# LPC1768.net
KiCad netlist of a schematic drawn in Altium Designer
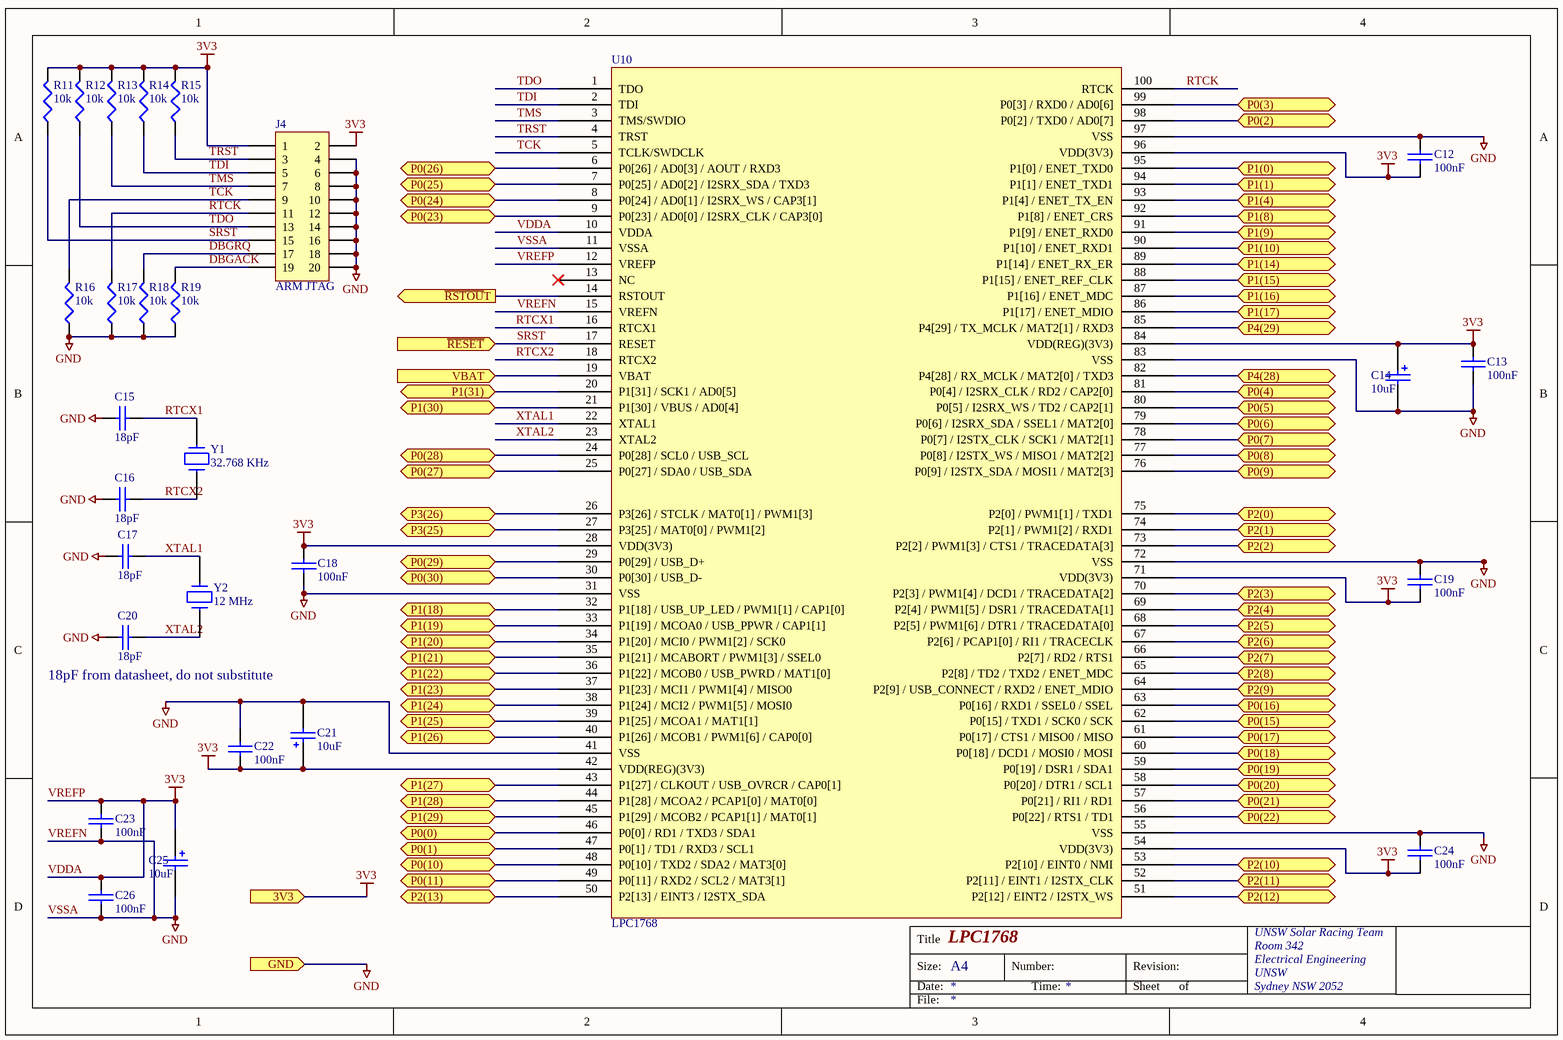
[diagram p0: LPC1768.SchDoc]

(export (version "E")
  (design (tool "Eeschema 10.0.6"))
  (components
    (comp (ref "C12")
      (value "100nF")
      (footprint "0603")
      (description "Capacitor")
      (libsource (lib "RCLDQ") (part "CAP"))
    )
    (comp (ref "C13")
      (value "100nF")
      (footprint "0603")
      (description "Capacitor")
      (libsource (lib "RCLDQ") (part "CAP"))
    )
    (comp (ref "C14")
      (value "10uF")
      (footprint "MCCT-CASEA")
      (description "Polarized Capacitor (Surface Mount)")
      (libsource (lib "RCLDQ") (part "CAP POL3"))
    )
    (comp (ref "C15")
      (value "18pF")
      (footprint "0603")
      (description "Capacitor")
      (libsource (lib "*") (part "CAP"))
    )
    (comp (ref "C16")
      (value "18pF")
      (footprint "0603")
      (description "Capacitor")
      (libsource (lib "*") (part "CAP"))
    )
    (comp (ref "C17")
      (value "18pF")
      (footprint "0603")
      (description "Capacitor")
      (libsource (lib "*") (part "CAP"))
    )
    (comp (ref "C18")
      (value "100nF")
      (footprint "0603")
      (description "Capacitor")
      (libsource (lib "RCLDQ") (part "CAP"))
    )
    (comp (ref "C19")
      (value "100nF")
      (footprint "0603")
      (description "Capacitor")
      (libsource (lib "RCLDQ") (part "CAP"))
    )
    (comp (ref "C20")
      (value "18pF")
      (footprint "0603")
      (description "Capacitor")
      (libsource (lib "*") (part "CAP"))
    )
    (comp (ref "C21")
      (value "10uF")
      (footprint "MCCT-CASEA")
      (description "Polarized Capacitor (Surface Mount)")
      (libsource (lib "RCLDQ") (part "CAP POL3"))
    )
    (comp (ref "C22")
      (value "100nF")
      (footprint "0603")
      (description "Capacitor")
      (libsource (lib "RCLDQ") (part "CAP"))
    )
    (comp (ref "C23")
      (value "100nF")
      (footprint "0603")
      (description "Capacitor")
      (libsource (lib "RCLDQ") (part "CAP"))
    )
    (comp (ref "C24")
      (value "100nF")
      (footprint "0603")
      (description "Capacitor")
      (libsource (lib "RCLDQ") (part "CAP"))
    )
    (comp (ref "C25")
      (value "10uF")
      (footprint "MCCT-CASEA")
      (description "Polarized Capacitor (Surface Mount)")
      (libsource (lib "RCLDQ") (part "CAP POL3"))
    )
    (comp (ref "C26")
      (value "100nF")
      (footprint "0603")
      (description "Capacitor")
      (libsource (lib "RCLDQ") (part "CAP"))
    )
    (comp (ref "J4")
      (value "ARM JTAG")
      (footprint "HDR2X10")
      (description "Header, 10-Pin, Dual row")
      (libsource (lib "Miscellaneous Connectors") (part "Header 10X2"))
    )
    (comp (ref "R11")
      (value "10k")
      (footprint "0603")
      (description "Resistor")
      (libsource (lib "RCLDQ") (part "RES1"))
    )
    (comp (ref "R12")
      (value "10k")
      (footprint "0603")
      (description "Resistor")
      (libsource (lib "RCLDQ") (part "RES1"))
    )
    (comp (ref "R13")
      (value "10k")
      (footprint "0603")
      (description "Resistor")
      (libsource (lib "RCLDQ") (part "RES1"))
    )
    (comp (ref "R14")
      (value "10k")
      (footprint "0603")
      (description "Resistor")
      (libsource (lib "RCLDQ") (part "RES1"))
    )
    (comp (ref "R15")
      (value "10k")
      (footprint "0603")
      (description "Resistor")
      (libsource (lib "RCLDQ") (part "RES1"))
    )
    (comp (ref "R16")
      (value "10k")
      (footprint "0603")
      (description "Resistor")
      (libsource (lib "RCLDQ") (part "RES1"))
    )
    (comp (ref "R17")
      (value "10k")
      (footprint "0603")
      (description "Resistor")
      (libsource (lib "RCLDQ") (part "RES1"))
    )
    (comp (ref "R18")
      (value "10k")
      (footprint "0603")
      (description "Resistor")
      (libsource (lib "RCLDQ") (part "RES1"))
    )
    (comp (ref "R19")
      (value "10k")
      (footprint "0603")
      (description "Resistor")
      (libsource (lib "RCLDQ") (part "RES1"))
    )
    (comp (ref "U10")
      (value "LPC1768")
      (footprint "QFP100")
      (description "NXP Cortex-M3 Microcontroller, 100pin 100MHz")
      (libsource (lib "sion") (part "LPC1768"))
    )
    (comp (ref "Y1")
      (value "32.768 KHz")
      (footprint "WATCHA")
      (description "Crystal")
      (libsource (lib "*") (part "CRYSTAL"))
    )
    (comp (ref "Y2")
      (value "12 MHz")
      (footprint "HC49/4H")
      (description "Crystal")
      (libsource (lib "*") (part "CRYSTAL"))
    )
  )
  (nets
    (net (code "1") (name "/DBGACK") (class "Default")
      (node (ref "J4") (pin "19") (pinfunction "19_19") (pintype "passive"))
      (node (ref "R19") (pin "2") (pinfunction "2_2") (pintype "passive"))
    )
    (net (code "2") (name "/DBGRQ") (class "Default")
      (node (ref "J4") (pin "17") (pinfunction "17_17") (pintype "passive"))
      (node (ref "R18") (pin "2") (pinfunction "2_2") (pintype "passive"))
    )
    (net (code "3") (name "/P0(0)") (class "Default")
      (node (ref "U10") (pin "46") (pinfunction "P0[0]_/_RD1_/_TXD3_/_SDA1_46") (pintype "passive"))
    )
    (net (code "4") (name "/P0(1)") (class "Default")
      (node (ref "U10") (pin "47") (pinfunction "P0[1]_/_TD1_/_RXD3_/_SCL1_47") (pintype "passive"))
    )
    (net (code "5") (name "/P0(2)") (class "Default")
      (node (ref "U10") (pin "98") (pinfunction "P0[2]_/_TXD0_/_AD0[7]_98") (pintype "passive"))
    )
    (net (code "6") (name "/P0(3)") (class "Default")
      (node (ref "U10") (pin "99") (pinfunction "P0[3]_/_RXD0_/_AD0[6]_99") (pintype "passive"))
    )
    (net (code "7") (name "/P0(4)") (class "Default")
      (node (ref "U10") (pin "81") (pinfunction "P0[4]_/_I2SRX_CLK_/_RD2_/_CAP2[0]_81") (pintype "passive"))
    )
    (net (code "8") (name "/P0(5)") (class "Default")
      (node (ref "U10") (pin "80") (pinfunction "P0[5]_/_I2SRX_WS_/_TD2_/_CAP2[1]_80") (pintype "passive"))
    )
    (net (code "9") (name "/P0(6)") (class "Default")
      (node (ref "U10") (pin "79") (pinfunction "P0[6]_/_I2SRX_SDA_/_SSEL1_/_MAT2[0]_79") (pintype "passive"))
    )
    (net (code "10") (name "/P0(7)") (class "Default")
      (node (ref "U10") (pin "78") (pinfunction "P0[7]_/_I2STX_CLK_/_SCK1_/_MAT2[1]_78") (pintype "passive"))
    )
    (net (code "11") (name "/P0(8)") (class "Default")
      (node (ref "U10") (pin "77") (pinfunction "P0[8]_/_I2STX_WS_/_MISO1_/_MAT2[2]_77") (pintype "passive"))
    )
    (net (code "12") (name "/P0(9)") (class "Default")
      (node (ref "U10") (pin "76") (pinfunction "P0[9]_/_I2STX_SDA_/_MOSI1_/_MAT2[3]_76") (pintype "passive"))
    )
    (net (code "13") (name "/P0(10)") (class "Default")
      (node (ref "U10") (pin "48") (pinfunction "P0[10]_/_TXD2_/_SDA2_/_MAT3[0]_48") (pintype "passive"))
    )
    (net (code "14") (name "/P0(11)") (class "Default")
      (node (ref "U10") (pin "49") (pinfunction "P0[11]_/_RXD2_/_SCL2_/_MAT3[1]_49") (pintype "passive"))
    )
    (net (code "15") (name "/P0(15)") (class "Default")
      (node (ref "U10") (pin "62") (pinfunction "P0[15]_/_TXD1_/_SCK0_/_SCK_62") (pintype "passive"))
    )
    (net (code "16") (name "/P0(16)") (class "Default")
      (node (ref "U10") (pin "63") (pinfunction "P0[16]_/_RXD1_/_SSEL0_/_SSEL_63") (pintype "passive"))
    )
    (net (code "17") (name "/P0(17)") (class "Default")
      (node (ref "U10") (pin "61") (pinfunction "P0[17]_/_CTS1_/_MISO0_/_MISO_61") (pintype "passive"))
    )
    (net (code "18") (name "/P0(18)") (class "Default")
      (node (ref "U10") (pin "60") (pinfunction "P0[18]_/_DCD1_/_MOSI0_/_MOSI_60") (pintype "passive"))
    )
    (net (code "19") (name "/P0(19)") (class "Default")
      (node (ref "U10") (pin "59") (pinfunction "P0[19]_/_DSR1_/_SDA1_59") (pintype "passive"))
    )
    (net (code "20") (name "/P0(20)") (class "Default")
      (node (ref "U10") (pin "58") (pinfunction "P0[20]_/_DTR1_/_SCL1_58") (pintype "passive"))
    )
    (net (code "21") (name "/P0(21)") (class "Default")
      (node (ref "U10") (pin "57") (pinfunction "P0[21]_/_RI1_/_RD1_57") (pintype "passive"))
    )
    (net (code "22") (name "/P0(22)") (class "Default")
      (node (ref "U10") (pin "56") (pinfunction "P0[22]_/_RTS1_/_TD1_56") (pintype "passive"))
    )
    (net (code "23") (name "/P0(23)") (class "Default")
      (node (ref "U10") (pin "9") (pinfunction "P0[23]_/_AD0[0]_/_I2SRX_CLK_/_CAP3[0]_9") (pintype "passive"))
    )
    (net (code "24") (name "/P0(24)") (class "Default")
      (node (ref "U10") (pin "8") (pinfunction "P0[24]_/_AD0[1]_/_I2SRX_WS_/_CAP3[1]_8") (pintype "passive"))
    )
    (net (code "25") (name "/P0(25)") (class "Default")
      (node (ref "U10") (pin "7") (pinfunction "P0[25]_/_AD0[2]_/_I2SRX_SDA_/_TXD3_7") (pintype "passive"))
    )
    (net (code "26") (name "/P0(26)") (class "Default")
      (node (ref "U10") (pin "6") (pinfunction "P0[26]_/_AD0[3]_/_AOUT_/_RXD3_6") (pintype "passive"))
    )
    (net (code "27") (name "/P0(27)") (class "Default")
      (node (ref "U10") (pin "25") (pinfunction "P0[27]_/_SDA0_/_USB_SDA_25") (pintype "passive"))
    )
    (net (code "28") (name "/P0(28)") (class "Default")
      (node (ref "U10") (pin "24") (pinfunction "P0[28]_/_SCL0_/_USB_SCL_24") (pintype "passive"))
    )
    (net (code "29") (name "/P0(29)") (class "Default")
      (node (ref "U10") (pin "29") (pinfunction "P0[29]_/_USB_D+_29") (pintype "passive"))
    )
    (net (code "30") (name "/P0(30)") (class "Default")
      (node (ref "U10") (pin "30") (pinfunction "P0[30]_/_USB_D-_30") (pintype "passive"))
    )
    (net (code "31") (name "/P1(0)") (class "Default")
      (node (ref "U10") (pin "95") (pinfunction "P1[0]_/_ENET_TXD0_95") (pintype "passive"))
    )
    (net (code "32") (name "/P1(1)") (class "Default")
      (node (ref "U10") (pin "94") (pinfunction "P1[1]_/_ENET_TXD1_94") (pintype "passive"))
    )
    (net (code "33") (name "/P1(4)") (class "Default")
      (node (ref "U10") (pin "93") (pinfunction "P1[4]_/_ENET_TX_EN_93") (pintype "passive"))
    )
    (net (code "34") (name "/P1(8)") (class "Default")
      (node (ref "U10") (pin "92") (pinfunction "P1[8]_/_ENET_CRS_92") (pintype "passive"))
    )
    (net (code "35") (name "/P1(9)") (class "Default")
      (node (ref "U10") (pin "91") (pinfunction "P1[9]_/_ENET_RXD0_91") (pintype "passive"))
    )
    (net (code "36") (name "/P1(10)") (class "Default")
      (node (ref "U10") (pin "90") (pinfunction "P1[10]_/_ENET_RXD1_90") (pintype "passive"))
    )
    (net (code "37") (name "/P1(14)") (class "Default")
      (node (ref "U10") (pin "89") (pinfunction "P1[14]_/_ENET_RX_ER_89") (pintype "passive"))
    )
    (net (code "38") (name "/P1(15)") (class "Default")
      (node (ref "U10") (pin "88") (pinfunction "P1[15]_/_ENET_REF_CLK_88") (pintype "passive"))
    )
    (net (code "39") (name "/P1(16)") (class "Default")
      (node (ref "U10") (pin "87") (pinfunction "P1[16]_/_ENET_MDC_87") (pintype "passive"))
    )
    (net (code "40") (name "/P1(17)") (class "Default")
      (node (ref "U10") (pin "86") (pinfunction "P1[17]_/_ENET_MDIO_86") (pintype "passive"))
    )
    (net (code "41") (name "/P1(18)") (class "Default")
      (node (ref "U10") (pin "32") (pinfunction "P1[18]_/_USB_UP_LED_/_PWM1[1]_/_CAP1[0]_32") (pintype "passive"))
    )
    (net (code "42") (name "/P1(19)") (class "Default")
      (node (ref "U10") (pin "33") (pinfunction "P1[19]_/_MCOA0_/_USB_PPWR_/_CAP1[1]_33") (pintype "passive"))
    )
    (net (code "43") (name "/P1(20)") (class "Default")
      (node (ref "U10") (pin "34") (pinfunction "P1[20]_/_MCI0_/_PWM1[2]_/_SCK0_34") (pintype "passive"))
    )
    (net (code "44") (name "/P1(21)") (class "Default")
      (node (ref "U10") (pin "35") (pinfunction "P1[21]_/_MCABORT_/_PWM1[3]_/_SSEL0_35") (pintype "passive"))
    )
    (net (code "45") (name "/P1(22)") (class "Default")
      (node (ref "U10") (pin "36") (pinfunction "P1[22]_/_MCOB0_/_USB_PWRD_/_MAT1[0]_36") (pintype "passive"))
    )
    (net (code "46") (name "/P1(23)") (class "Default")
      (node (ref "U10") (pin "37") (pinfunction "P1[23]_/_MCI1_/_PWM1[4]_/_MISO0_37") (pintype "passive"))
    )
    (net (code "47") (name "/P1(24)") (class "Default")
      (node (ref "U10") (pin "38") (pinfunction "P1[24]_/_MCI2_/_PWM1[5]_/_MOSI0_38") (pintype "passive"))
    )
    (net (code "48") (name "/P1(25)") (class "Default")
      (node (ref "U10") (pin "39") (pinfunction "P1[25]_/_MCOA1_/_MAT1[1]_39") (pintype "passive"))
    )
    (net (code "49") (name "/P1(26)") (class "Default")
      (node (ref "U10") (pin "40") (pinfunction "P1[26]_/_MCOB1_/_PWM1[6]_/_CAP0[0]_40") (pintype "passive"))
    )
    (net (code "50") (name "/P1(27)") (class "Default")
      (node (ref "U10") (pin "43") (pinfunction "P1[27]_/_CLKOUT_/_USB_OVRCR_/_CAP0[1]_43") (pintype "passive"))
    )
    (net (code "51") (name "/P1(28)") (class "Default")
      (node (ref "U10") (pin "44") (pinfunction "P1[28]_/_MCOA2_/_PCAP1[0]_/_MAT0[0]_44") (pintype "passive"))
    )
    (net (code "52") (name "/P1(29)") (class "Default")
      (node (ref "U10") (pin "45") (pinfunction "P1[29]_/_MCOB2_/_PCAP1[1]_/_MAT0[1]_45") (pintype "passive"))
    )
    (net (code "53") (name "/P1(30)") (class "Default")
      (node (ref "U10") (pin "21") (pinfunction "P1[30]_/_VBUS_/_AD0[4]_21") (pintype "passive"))
    )
    (net (code "54") (name "/P1(31)") (class "Default")
      (node (ref "U10") (pin "20") (pinfunction "P1[31]_/_SCK1_/_AD0[5]_20") (pintype "passive"))
    )
    (net (code "55") (name "/P2(0)") (class "Default")
      (node (ref "U10") (pin "75") (pinfunction "P2[0]_/_PWM1[1]_/_TXD1_75") (pintype "passive"))
    )
    (net (code "56") (name "/P2(1)") (class "Default")
      (node (ref "U10") (pin "74") (pinfunction "P2[1]_/_PWM1[2]_/_RXD1_74") (pintype "passive"))
    )
    (net (code "57") (name "/P2(2)") (class "Default")
      (node (ref "U10") (pin "73") (pinfunction "P2[2]_/_PWM1[3]_/_CTS1_/_TRACEDATA[3]_73") (pintype "passive"))
    )
    (net (code "58") (name "/P2(3)") (class "Default")
      (node (ref "U10") (pin "70") (pinfunction "P2[3]_/_PWM1[4]_/_DCD1_/_TRACEDATA[2]_70") (pintype "passive"))
    )
    (net (code "59") (name "/P2(4)") (class "Default")
      (node (ref "U10") (pin "69") (pinfunction "P2[4]_/_PWM1[5]_/_DSR1_/_TRACEDATA[1]_69") (pintype "passive"))
    )
    (net (code "60") (name "/P2(5)") (class "Default")
      (node (ref "U10") (pin "68") (pinfunction "P2[5]_/_PWM1[6]_/_DTR1_/_TRACEDATA[0]_68") (pintype "passive"))
    )
    (net (code "61") (name "/P2(6)") (class "Default")
      (node (ref "U10") (pin "67") (pinfunction "P2[6]_/_PCAP1[0]_/_RI1_/_TRACECLK_67") (pintype "passive"))
    )
    (net (code "62") (name "/P2(7)") (class "Default")
      (node (ref "U10") (pin "66") (pinfunction "P2[7]_/_RD2_/_RTS1_66") (pintype "passive"))
    )
    (net (code "63") (name "/P2(8)") (class "Default")
      (node (ref "U10") (pin "65") (pinfunction "P2[8]_/_TD2_/_TXD2_/_ENET_MDC_65") (pintype "passive"))
    )
    (net (code "64") (name "/P2(9)") (class "Default")
      (node (ref "U10") (pin "64") (pinfunction "P2[9]_/_USB_CONNECT_/_RXD2_/_ENET_MDIO_64") (pintype "passive"))
    )
    (net (code "65") (name "/P2(10)") (class "Default")
      (node (ref "U10") (pin "53") (pinfunction "P2[10]_/_EINT0_/_NMI_53") (pintype "passive"))
    )
    (net (code "66") (name "/P2(11)") (class "Default")
      (node (ref "U10") (pin "52") (pinfunction "P2[11]_/_EINT1_/_I2STX_CLK_52") (pintype "passive"))
    )
    (net (code "67") (name "/P2(12)") (class "Default")
      (node (ref "U10") (pin "51") (pinfunction "P2[12]_/_EINT2_/_I2STX_WS_51") (pintype "passive"))
    )
    (net (code "68") (name "/P2(13)") (class "Default")
      (node (ref "U10") (pin "50") (pinfunction "P2[13]_/_EINT3_/_I2STX_SDA_50") (pintype "passive"))
    )
    (net (code "69") (name "/P3(25)") (class "Default")
      (node (ref "U10") (pin "27") (pinfunction "P3[25]_/_MAT0[0]_/_PWM1[2]_27") (pintype "passive"))
    )
    (net (code "70") (name "/P3(26)") (class "Default")
      (node (ref "U10") (pin "26") (pinfunction "P3[26]_/_STCLK_/_MAT0[1]_/_PWM1[3]_26") (pintype "passive"))
    )
    (net (code "71") (name "/P4(28)") (class "Default")
      (node (ref "U10") (pin "82") (pinfunction "P4[28]_/_RX_MCLK_/_MAT2[0]_/_TXD3_82") (pintype "passive"))
    )
    (net (code "72") (name "/P4(29)") (class "Default")
      (node (ref "U10") (pin "85") (pinfunction "P4[29]_/_TX_MCLK_/_MAT2[1]_/_RXD3_85") (pintype "passive"))
    )
    (net (code "73") (name "/RTCK") (class "Default")
      (node (ref "J4") (pin "11") (pinfunction "11_11") (pintype "passive"))
      (node (ref "R17") (pin "2") (pinfunction "2_2") (pintype "passive"))
      (node (ref "U10") (pin "100") (pinfunction "RTCK_100") (pintype "passive"))
    )
    (net (code "74") (name "/RTCX1") (class "Default")
      (node (ref "C15") (pin "1") (pinfunction "1_1") (pintype "passive"))
      (node (ref "U10") (pin "16") (pinfunction "RTCX1_16") (pintype "passive"))
      (node (ref "Y1") (pin "2") (pinfunction "2_2") (pintype "passive"))
    )
    (net (code "75") (name "/RTCX2") (class "Default")
      (node (ref "C16") (pin "1") (pinfunction "1_1") (pintype "passive"))
      (node (ref "U10") (pin "18") (pinfunction "RTCX2_18") (pintype "passive"))
      (node (ref "Y1") (pin "1") (pinfunction "1_1") (pintype "passive"))
    )
    (net (code "76") (name "/SRST") (class "Default")
      (node (ref "J4") (pin "15") (pinfunction "15_15") (pintype "passive"))
      (node (ref "R11") (pin "1") (pinfunction "1_1") (pintype "passive"))
      (node (ref "U10") (pin "17") (pinfunction "RESET_17") (pintype "passive"))
    )
    (net (code "77") (name "/TCK") (class "Default")
      (node (ref "J4") (pin "9") (pinfunction "9_9") (pintype "passive"))
      (node (ref "R16") (pin "2") (pinfunction "2_2") (pintype "passive"))
      (node (ref "U10") (pin "5") (pinfunction "TCLK/SWDCLK_5") (pintype "passive"))
    )
    (net (code "78") (name "/TDI") (class "Default")
      (node (ref "J4") (pin "5") (pinfunction "5_5") (pintype "passive"))
      (node (ref "R14") (pin "1") (pinfunction "1_1") (pintype "passive"))
      (node (ref "U10") (pin "2") (pinfunction "TDI_2") (pintype "passive"))
    )
    (net (code "79") (name "/TDO") (class "Default")
      (node (ref "J4") (pin "13") (pinfunction "13_13") (pintype "passive"))
      (node (ref "R12") (pin "1") (pinfunction "1_1") (pintype "passive"))
      (node (ref "U10") (pin "1") (pinfunction "TDO_1") (pintype "passive"))
    )
    (net (code "80") (name "/TMS") (class "Default")
      (node (ref "J4") (pin "7") (pinfunction "7_7") (pintype "passive"))
      (node (ref "R13") (pin "1") (pinfunction "1_1") (pintype "passive"))
      (node (ref "U10") (pin "3") (pinfunction "TMS/SWDIO_3") (pintype "passive"))
    )
    (net (code "81") (name "/TRST") (class "Default")
      (node (ref "J4") (pin "3") (pinfunction "3_3") (pintype "passive"))
      (node (ref "R15") (pin "1") (pinfunction "1_1") (pintype "passive"))
      (node (ref "U10") (pin "4") (pinfunction "TRST_4") (pintype "passive"))
    )
    (net (code "82") (name "/VBAT") (class "Default")
      (node (ref "U10") (pin "19") (pinfunction "VBAT_19") (pintype "passive"))
    )
    (net (code "83") (name "/XTAL1") (class "Default")
      (node (ref "C17") (pin "1") (pinfunction "1_1") (pintype "passive"))
      (node (ref "U10") (pin "22") (pinfunction "XTAL1_22") (pintype "passive"))
      (node (ref "Y2") (pin "1") (pinfunction "1_1") (pintype "passive"))
    )
    (net (code "84") (name "/XTAL2") (class "Default")
      (node (ref "C20") (pin "1") (pinfunction "1_1") (pintype "passive"))
      (node (ref "U10") (pin "23") (pinfunction "XTAL2_23") (pintype "passive"))
      (node (ref "Y2") (pin "2") (pinfunction "2_2") (pintype "passive"))
    )
    (net (code "85") (name "/~{RSTOU}T") (class "Default")
      (node (ref "U10") (pin "14") (pinfunction "RSTOUT_14") (pintype "passive"))
    )
    (net (code "86") (name "3V3") (class "Default")
      (node (ref "C12") (pin "2") (pinfunction "2_2") (pintype "passive"))
      (node (ref "C13") (pin "1") (pinfunction "1_1") (pintype "passive"))
      (node (ref "C14") (pin "1") (pinfunction "1_1") (pintype "passive"))
      (node (ref "C18") (pin "1") (pinfunction "1_1") (pintype "passive"))
      (node (ref "C19") (pin "2") (pinfunction "2_2") (pintype "passive"))
      (node (ref "C21") (pin "1") (pinfunction "1_1") (pintype "passive"))
      (node (ref "C22") (pin "2") (pinfunction "2_2") (pintype "passive"))
      (node (ref "C23") (pin "1") (pinfunction "1_1") (pintype "passive"))
      (node (ref "C24") (pin "2") (pinfunction "2_2") (pintype "passive"))
      (node (ref "C25") (pin "1") (pinfunction "1_1") (pintype "passive"))
      (node (ref "C26") (pin "1") (pinfunction "1_1") (pintype "passive"))
      (node (ref "J4") (pin "1") (pinfunction "1_1") (pintype "passive"))
      (node (ref "J4") (pin "2") (pinfunction "2_2") (pintype "passive"))
      (node (ref "R11") (pin "2") (pinfunction "2_2") (pintype "passive"))
      (node (ref "R12") (pin "2") (pinfunction "2_2") (pintype "passive"))
      (node (ref "R13") (pin "2") (pinfunction "2_2") (pintype "passive"))
      (node (ref "R14") (pin "2") (pinfunction "2_2") (pintype "passive"))
      (node (ref "R15") (pin "2") (pinfunction "2_2") (pintype "passive"))
      (node (ref "U10") (pin "10") (pinfunction "VDDA_10") (pintype "passive"))
      (node (ref "U10") (pin "12") (pinfunction "VREFP_12") (pintype "passive"))
      (node (ref "U10") (pin "28") (pinfunction "VDD(3V3)_28") (pintype "passive"))
      (node (ref "U10") (pin "42") (pinfunction "VDD(REG)(3V3)_42") (pintype "passive"))
      (node (ref "U10") (pin "54") (pinfunction "VDD(3V3)_54") (pintype "passive"))
      (node (ref "U10") (pin "71") (pinfunction "VDD(3V3)_71") (pintype "passive"))
      (node (ref "U10") (pin "84") (pinfunction "VDD(REG)(3V3)_84") (pintype "passive"))
      (node (ref "U10") (pin "96") (pinfunction "VDD(3V3)_96") (pintype "passive"))
    )
    (net (code "87") (name "GND") (class "Default")
      (node (ref "C12") (pin "1") (pinfunction "1_1") (pintype "passive"))
      (node (ref "C13") (pin "2") (pinfunction "2_2") (pintype "passive"))
      (node (ref "C14") (pin "2") (pinfunction "2_2") (pintype "passive"))
      (node (ref "C15") (pin "2") (pinfunction "2_2") (pintype "passive"))
      (node (ref "C16") (pin "2") (pinfunction "2_2") (pintype "passive"))
      (node (ref "C17") (pin "2") (pinfunction "2_2") (pintype "passive"))
      (node (ref "C18") (pin "2") (pinfunction "2_2") (pintype "passive"))
      (node (ref "C19") (pin "1") (pinfunction "1_1") (pintype "passive"))
      (node (ref "C20") (pin "2") (pinfunction "2_2") (pintype "passive"))
      (node (ref "C21") (pin "2") (pinfunction "2_2") (pintype "passive"))
      (node (ref "C22") (pin "1") (pinfunction "1_1") (pintype "passive"))
      (node (ref "C23") (pin "2") (pinfunction "2_2") (pintype "passive"))
      (node (ref "C24") (pin "1") (pinfunction "1_1") (pintype "passive"))
      (node (ref "C25") (pin "2") (pinfunction "2_2") (pintype "passive"))
      (node (ref "C26") (pin "2") (pinfunction "2_2") (pintype "passive"))
      (node (ref "J4") (pin "10") (pinfunction "10_10") (pintype "passive"))
      (node (ref "J4") (pin "12") (pinfunction "12_12") (pintype "passive"))
      (node (ref "J4") (pin "14") (pinfunction "14_14") (pintype "passive"))
      (node (ref "J4") (pin "16") (pinfunction "16_16") (pintype "passive"))
      (node (ref "J4") (pin "18") (pinfunction "18_18") (pintype "passive"))
      (node (ref "J4") (pin "20") (pinfunction "20_20") (pintype "passive"))
      (node (ref "J4") (pin "4") (pinfunction "4_4") (pintype "passive"))
      (node (ref "J4") (pin "6") (pinfunction "6_6") (pintype "passive"))
      (node (ref "J4") (pin "8") (pinfunction "8_8") (pintype "passive"))
      (node (ref "R16") (pin "1") (pinfunction "1_1") (pintype "passive"))
      (node (ref "R17") (pin "1") (pinfunction "1_1") (pintype "passive"))
      (node (ref "R18") (pin "1") (pinfunction "1_1") (pintype "passive"))
      (node (ref "R19") (pin "1") (pinfunction "1_1") (pintype "passive"))
      (node (ref "U10") (pin "11") (pinfunction "VSSA_11") (pintype "passive"))
      (node (ref "U10") (pin "15") (pinfunction "VREFN_15") (pintype "passive"))
      (node (ref "U10") (pin "31") (pinfunction "VSS_31") (pintype "passive"))
      (node (ref "U10") (pin "41") (pinfunction "VSS_41") (pintype "passive"))
      (node (ref "U10") (pin "55") (pinfunction "VSS_55") (pintype "passive"))
      (node (ref "U10") (pin "72") (pinfunction "VSS_72") (pintype "passive"))
      (node (ref "U10") (pin "83") (pinfunction "VSS_83") (pintype "passive"))
      (node (ref "U10") (pin "97") (pinfunction "VSS_97") (pintype "passive"))
    )
    (net (code "88") (name "unconnected-(U10-NC-Pad13)") (class "Default")
      (node (ref "U10") (pin "13") (pinfunction "NC_13") (pintype "passive+no_connect"))
    )
  )
)
